# Stereo_L_R_TPA3138D2.net
KiCad netlist of a schematic drawn in Altium Designer
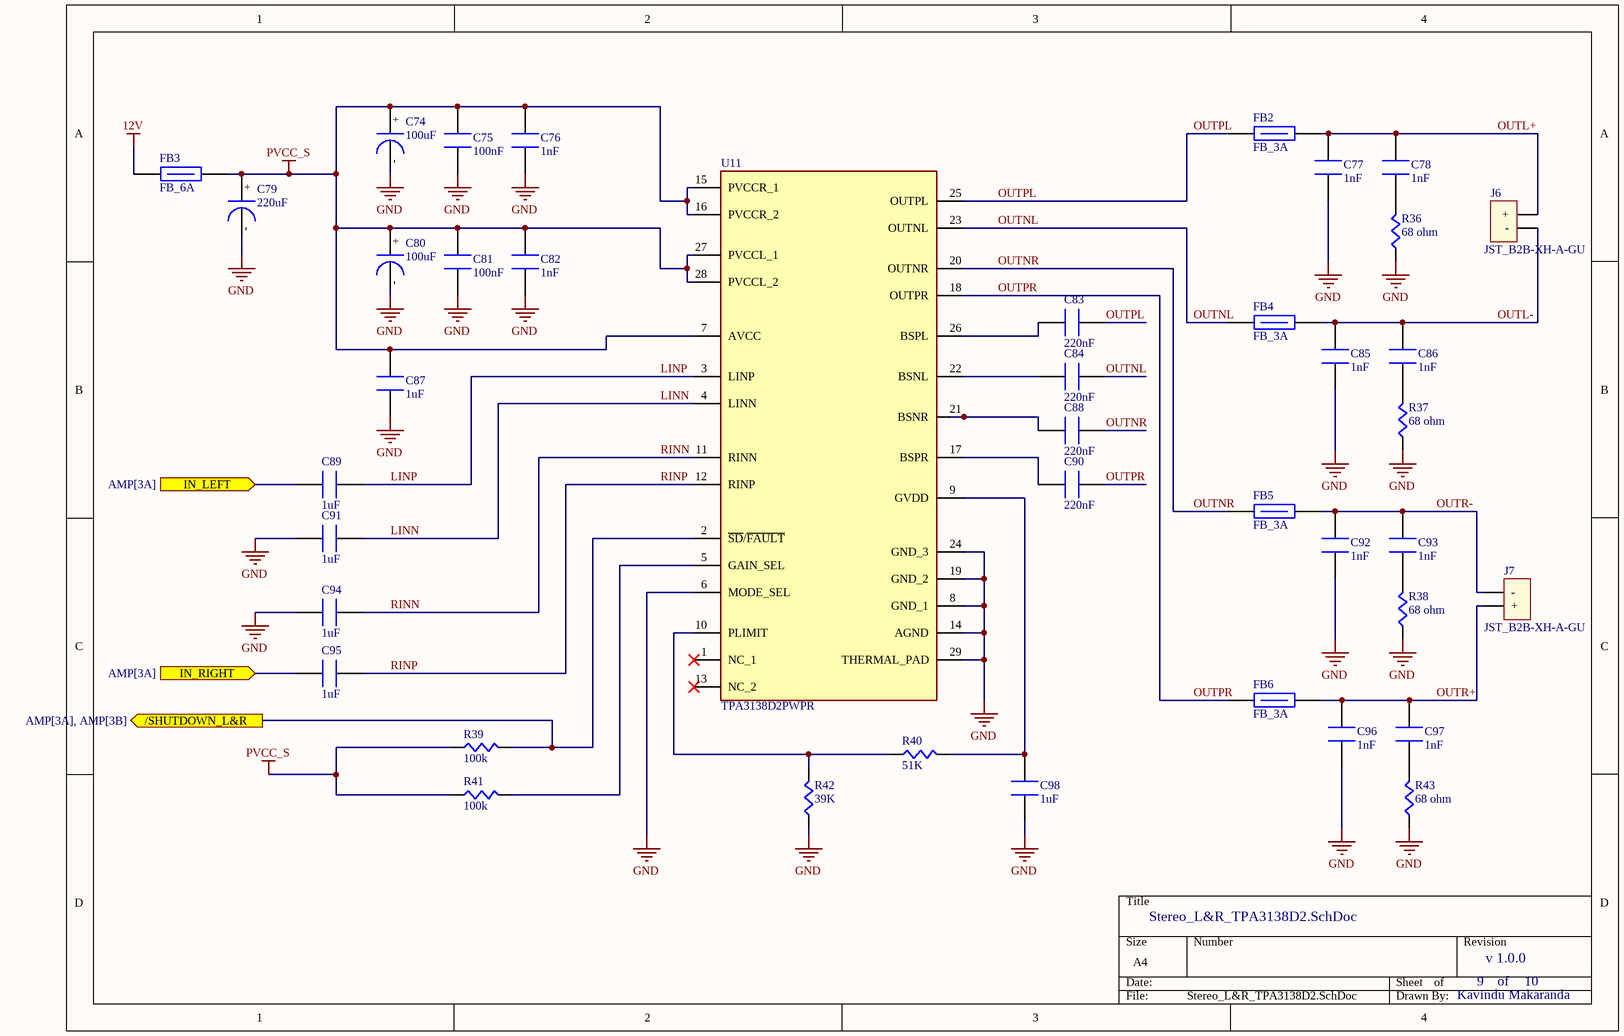
[diagram p0: Stereo_L&R_TPA3138D2.SchDoc]

(export (version "E")
  (design (tool "Eeschema 10.0.6"))
  (components
    (comp (ref "C74")
      (value "100uF")
      (footprint "CAPD6.3XL6.3X77M")
      (libsource (lib "Schlib1") (part "CPD6.3XL7.7_100uF_POLY"))
    )
    (comp (ref "C75")
      (value "100nF")
      (footprint "CAPC0603X8N")
      (libsource (lib "Schlib1") (part "CC0603_100nF_X7R"))
    )
    (comp (ref "C76")
      (value "1nF")
      (footprint "CAPC0603X8N")
      (libsource (lib "Schlib1") (part "CC0603_1nF_X7R"))
    )
    (comp (ref "C77")
      (value "1nF")
      (footprint "CAPC0603X8N")
      (description "C106246, CC0603JRNPO9BN102, 1nF 50V NP0 ±5% 0603 Multilayer Ceramic Capacitors MLCC - SMD/SMT ROHS")
      (libsource (lib "Schlib1") (part "CC0603_1nF_NPO"))
    )
    (comp (ref "C78")
      (value "1nF")
      (footprint "CAPC0603X8N")
      (description "C106246, CC0603JRNPO9BN102, 1nF 50V NP0 ±5% 0603 Multilayer Ceramic Capacitors MLCC - SMD/SMT ROHS")
      (libsource (lib "Schlib1") (part "CC0603_1nF_NPO"))
    )
    (comp (ref "C79")
      (value "220uF")
      (footprint "CAPD6.3XL6.3X77M")
      (libsource (lib "Schlib1") (part "CPD6.3XL7.7_220uF_POLY"))
    )
    (comp (ref "C80")
      (value "100uF")
      (footprint "CAPD6.3XL6.3X77M")
      (libsource (lib "Schlib1") (part "CPD6.3XL7.7_100uF_POLY"))
    )
    (comp (ref "C81")
      (value "100nF")
      (footprint "CAPC0603X8N")
      (libsource (lib "Schlib1") (part "CC0603_100nF_X7R"))
    )
    (comp (ref "C82")
      (value "1nF")
      (footprint "CAPC0603X8N")
      (libsource (lib "Schlib1") (part "CC0603_1nF_X7R"))
    )
    (comp (ref "C83")
      (value "220nF")
      (footprint "CAPC1206X18N")
      (libsource (lib "Schlib1") (part "CC1206_220nF_NPO"))
    )
    (comp (ref "C84")
      (value "220nF")
      (footprint "CAPC1206X18N")
      (libsource (lib "Schlib1") (part "CC1206_220nF_NPO"))
    )
    (comp (ref "C85")
      (value "1nF")
      (footprint "CAPC0603X8N")
      (description "C106246, CC0603JRNPO9BN102, 1nF 50V NP0 ±5% 0603 Multilayer Ceramic Capacitors MLCC - SMD/SMT ROHS")
      (libsource (lib "Schlib1") (part "CC0603_1nF_NPO"))
    )
    (comp (ref "C86")
      (value "1nF")
      (footprint "CAPC0603X8N")
      (description "C106246, CC0603JRNPO9BN102, 1nF 50V NP0 ±5% 0603 Multilayer Ceramic Capacitors MLCC - SMD/SMT ROHS")
      (libsource (lib "Schlib1") (part "CC0603_1nF_NPO"))
    )
    (comp (ref "C87")
      (value "1uF")
      (footprint "CAP0805X13N")
      (description "C28323, CL21B105KBFNNNE, 1uF 50V X7R ±10% 0805 Multilayer Ceramic Capacitors MLCC - SMD/SMT ROHS")
      (libsource (lib "Schlib1") (part "CC0805_1uF_X7R"))
    )
    (comp (ref "C88")
      (value "220nF")
      (footprint "CAPC1206X18N")
      (libsource (lib "Schlib1") (part "CC1206_220nF_NPO"))
    )
    (comp (ref "C89")
      (value "1uF")
      (footprint "CAP0805X13N")
      (description "C28323, CL21B105KBFNNNE, 1uF 50V X7R ±10% 0805 Multilayer Ceramic Capacitors MLCC - SMD/SMT ROHS")
      (libsource (lib "Schlib1") (part "CC0805_1uF_X7R"))
    )
    (comp (ref "C90")
      (value "220nF")
      (footprint "CAPC1206X18N")
      (libsource (lib "Schlib1") (part "CC1206_220nF_NPO"))
    )
    (comp (ref "C91")
      (value "1uF")
      (footprint "CAP0805X13N")
      (description "C28323, CL21B105KBFNNNE, 1uF 50V X7R ±10% 0805 Multilayer Ceramic Capacitors MLCC - SMD/SMT ROHS")
      (libsource (lib "Schlib1") (part "CC0805_1uF_X7R"))
    )
    (comp (ref "C92")
      (value "1nF")
      (footprint "CAPC0603X8N")
      (description "C106246, CC0603JRNPO9BN102, 1nF 50V NP0 ±5% 0603 Multilayer Ceramic Capacitors MLCC - SMD/SMT ROHS")
      (libsource (lib "Schlib1") (part "CC0603_1nF_NPO"))
    )
    (comp (ref "C93")
      (value "1nF")
      (footprint "CAPC0603X8N")
      (description "C106246, CC0603JRNPO9BN102, 1nF 50V NP0 ±5% 0603 Multilayer Ceramic Capacitors MLCC - SMD/SMT ROHS")
      (libsource (lib "Schlib1") (part "CC0603_1nF_NPO"))
    )
    (comp (ref "C94")
      (value "1uF")
      (footprint "CAP0805X13N")
      (description "C28323, CL21B105KBFNNNE, 1uF 50V X7R ±10% 0805 Multilayer Ceramic Capacitors MLCC - SMD/SMT ROHS")
      (libsource (lib "Schlib1") (part "CC0805_1uF_X7R"))
    )
    (comp (ref "C95")
      (value "1uF")
      (footprint "CAP0805X13N")
      (description "C28323, CL21B105KBFNNNE, 1uF 50V X7R ±10% 0805 Multilayer Ceramic Capacitors MLCC - SMD/SMT ROHS")
      (libsource (lib "Schlib1") (part "CC0805_1uF_X7R"))
    )
    (comp (ref "C96")
      (value "1nF")
      (footprint "CAPC0603X8N")
      (description "C106246, CC0603JRNPO9BN102, 1nF 50V NP0 ±5% 0603 Multilayer Ceramic Capacitors MLCC - SMD/SMT ROHS")
      (libsource (lib "Schlib1") (part "CC0603_1nF_NPO"))
    )
    (comp (ref "C97")
      (value "1nF")
      (footprint "CAPC0603X8N")
      (description "C106246, CC0603JRNPO9BN102, 1nF 50V NP0 ±5% 0603 Multilayer Ceramic Capacitors MLCC - SMD/SMT ROHS")
      (libsource (lib "Schlib1") (part "CC0603_1nF_NPO"))
    )
    (comp (ref "C98")
      (value "1uF")
      (footprint "CAP0805X13N")
      (description "C28323, CL21B105KBFNNNE, 1uF 50V X7R ±10% 0805 Multilayer Ceramic Capacitors MLCC - SMD/SMT ROHS")
      (libsource (lib "Schlib1") (part "CC0805_1uF_X7R"))
    )
    (comp (ref "FB2")
      (value "FB_3A")
      (footprint "FB0603X08N")
      (description "C107332, MPZ1608S101ATAH0, -55℃~+125℃ 1 100Ω@100MHz 30mΩ 3A ±25% 0603 Ferrite Beads ROHS")
      (libsource (lib "Schlib1") (part "FB0603_3A"))
    )
    (comp (ref "FB3")
      (value "FB_6A")
      (footprint "FB0805X12N")
      (description "C136227, MPZ2012S300AT000, -55℃~+125℃ 1 10mΩ 30Ω@100MHz 6A ±25% 0805 Ferrite Beads ROHS")
      (libsource (lib "Schlib1") (part "FB0805_6A"))
    )
    (comp (ref "FB4")
      (value "FB_3A")
      (footprint "FB0603X08N")
      (description "C107332, MPZ1608S101ATAH0, -55℃~+125℃ 1 100Ω@100MHz 30mΩ 3A ±25% 0603 Ferrite Beads ROHS")
      (libsource (lib "Schlib1") (part "FB0603_3A"))
    )
    (comp (ref "FB5")
      (value "FB_3A")
      (footprint "FB0603X08N")
      (description "C107332, MPZ1608S101ATAH0, -55℃~+125℃ 1 100Ω@100MHz 30mΩ 3A ±25% 0603 Ferrite Beads ROHS")
      (libsource (lib "Schlib1") (part "FB0603_3A"))
    )
    (comp (ref "FB6")
      (value "FB_3A")
      (footprint "FB0603X08N")
      (description "C107332, MPZ1608S101ATAH0, -55℃~+125℃ 1 100Ω@100MHz 30mΩ 3A ±25% 0603 Ferrite Beads ROHS")
      (libsource (lib "Schlib1") (part "FB0603_3A"))
    )
    (comp (ref "J6")
      (value "JST_B2B-XH-A-GU")
      (footprint "JST_B2B_XH_A_GU")
      (libsource (lib "") (part "JST_B2B-XH-A-GU_1"))
    )
    (comp (ref "J7")
      (value "JST_B2B-XH-A-GU")
      (footprint "JST_B2B_XH_A_GU")
      (libsource (lib "Schlib1") (part "JST_B2B-XH-A-GU"))
    )
    (comp (ref "R36")
      (value "68 ohm")
      (footprint "RECS0603X45N")
      (libsource (lib "Schlib1") (part "RESC0603_68_THIN"))
    )
    (comp (ref "R37")
      (value "68 ohm")
      (footprint "RECS0603X45N")
      (libsource (lib "Schlib1") (part "RESC0603_68_THIN"))
    )
    (comp (ref "R38")
      (value "68 ohm")
      (footprint "RECS0603X45N")
      (libsource (lib "Schlib1") (part "RESC0603_68_THIN"))
    )
    (comp (ref "R39")
      (value "100k")
      (footprint "RECS0603X45N")
      (libsource (lib "Schlib1") (part "RESC0603_100K_THIN"))
    )
    (comp (ref "R40")
      (value "51K")
      (footprint "RECS0603X45N")
      (libsource (lib "Schlib1") (part "RESC0603_51K_THICK"))
    )
    (comp (ref "R41")
      (value "100k")
      (footprint "RECS0603X45N")
      (libsource (lib "Schlib1") (part "RESC0603_100K_THIN"))
    )
    (comp (ref "R42")
      (value "39K")
      (footprint "RECS0603X45N")
      (libsource (lib "Schlib1") (part "RESC0603_39K_THICK"))
    )
    (comp (ref "R43")
      (value "68 ohm")
      (footprint "RECS0603X45N")
      (libsource (lib "Schlib1") (part "RESC0603_68_THIN"))
    )
    (comp (ref "U11")
      (value "TPA3138D2PWPR")
      (footprint "SOP65P640X120-29N")
      (fields (field (name "MOUSER PART NUMBER") "595-TPA3138D2PWPR"))
      (libsource (lib "Schlib1") (part "TPA3138D2PWPR"))
    )
  )
  (nets
    (net (code "1") (name "/IN_LEFT") (class "Default")
      (node (ref "C89") (pin "1") (pinfunction "1_1") (pintype "passive"))
    )
    (net (code "2") (name "/IN_RIGHT") (class "Default")
      (node (ref "C95") (pin "1") (pinfunction "1_1") (pintype "passive"))
    )
    (net (code "3") (name "/LINN") (class "Default")
      (node (ref "C91") (pin "2") (pinfunction "2_2") (pintype "passive"))
      (node (ref "U11") (pin "4") (pinfunction "LINN_4") (pintype "passive"))
    )
    (net (code "4") (name "/LINP") (class "Default")
      (node (ref "C89") (pin "2") (pinfunction "2_2") (pintype "passive"))
      (node (ref "U11") (pin "3") (pinfunction "LINP_3") (pintype "passive"))
    )
    (net (code "5") (name "/OUTL+") (class "Default")
      (node (ref "C77") (pin "2") (pinfunction "2_2") (pintype "passive"))
      (node (ref "C78") (pin "2") (pinfunction "2_2") (pintype "passive"))
      (node (ref "FB2") (pin "2") (pinfunction "2_2") (pintype "passive"))
      (node (ref "J6") (pin "1") (pinfunction "+_1") (pintype "passive"))
    )
    (net (code "6") (name "/OUTL-") (class "Default")
      (node (ref "C85") (pin "2") (pinfunction "2_2") (pintype "passive"))
      (node (ref "C86") (pin "2") (pinfunction "2_2") (pintype "passive"))
      (node (ref "FB4") (pin "2") (pinfunction "2_2") (pintype "passive"))
      (node (ref "J6") (pin "2") (pinfunction "-_2") (pintype "passive"))
    )
    (net (code "7") (name "/OUTNL") (class "Default")
      (node (ref "C84") (pin "2") (pinfunction "2_2") (pintype "passive"))
      (node (ref "FB4") (pin "1") (pinfunction "1_1") (pintype "passive"))
      (node (ref "U11") (pin "23") (pinfunction "OUTNL_23") (pintype "passive"))
    )
    (net (code "8") (name "/OUTNR") (class "Default")
      (node (ref "C88") (pin "2") (pinfunction "2_2") (pintype "passive"))
      (node (ref "FB5") (pin "1") (pinfunction "1_1") (pintype "passive"))
      (node (ref "U11") (pin "20") (pinfunction "OUTNR_20") (pintype "passive"))
    )
    (net (code "9") (name "/OUTPL") (class "Default")
      (node (ref "C83") (pin "2") (pinfunction "2_2") (pintype "passive"))
      (node (ref "FB2") (pin "1") (pinfunction "1_1") (pintype "passive"))
      (node (ref "U11") (pin "25") (pinfunction "OUTPL_25") (pintype "passive"))
    )
    (net (code "10") (name "/OUTPR") (class "Default")
      (node (ref "C90") (pin "2") (pinfunction "2_2") (pintype "passive"))
      (node (ref "FB6") (pin "1") (pinfunction "1_1") (pintype "passive"))
      (node (ref "U11") (pin "18") (pinfunction "OUTPR_18") (pintype "passive"))
    )
    (net (code "11") (name "/OUTR+") (class "Default")
      (node (ref "C96") (pin "2") (pinfunction "2_2") (pintype "passive"))
      (node (ref "C97") (pin "2") (pinfunction "2_2") (pintype "passive"))
      (node (ref "FB6") (pin "2") (pinfunction "2_2") (pintype "passive"))
      (node (ref "J7") (pin "1") (pinfunction "+_1") (pintype "passive"))
    )
    (net (code "12") (name "/OUTR-") (class "Default")
      (node (ref "C92") (pin "2") (pinfunction "2_2") (pintype "passive"))
      (node (ref "C93") (pin "2") (pinfunction "2_2") (pintype "passive"))
      (node (ref "FB5") (pin "2") (pinfunction "2_2") (pintype "passive"))
      (node (ref "J7") (pin "2") (pinfunction "-_2") (pintype "passive"))
    )
    (net (code "13") (name "/RINN") (class "Default")
      (node (ref "C94") (pin "2") (pinfunction "2_2") (pintype "passive"))
      (node (ref "U11") (pin "11") (pinfunction "RINN_11") (pintype "passive"))
    )
    (net (code "14") (name "/RINP") (class "Default")
      (node (ref "C95") (pin "2") (pinfunction "2_2") (pintype "passive"))
      (node (ref "U11") (pin "12") (pinfunction "RINP_12") (pintype "passive"))
    )
    (net (code "15") (name "/{slash}SHUTDOWN_L&R") (class "Default")
      (node (ref "R39") (pin "2") (pinfunction "2_2") (pintype "passive"))
      (node (ref "U11") (pin "2") (pinfunction "~{SD}/~{FAULT}_2") (pintype "passive"))
    )
    (net (code "16") (name "12V") (class "Default")
      (node (ref "FB3") (pin "1") (pinfunction "1_1") (pintype "passive"))
    )
    (net (code "17") (name "GND") (class "Default")
      (node (ref "C74") (pin "2") (pinfunction "2_2") (pintype "passive"))
      (node (ref "C75") (pin "1") (pinfunction "1_1") (pintype "passive"))
      (node (ref "C76") (pin "1") (pinfunction "1_1") (pintype "passive"))
      (node (ref "C77") (pin "1") (pinfunction "1_1") (pintype "passive"))
      (node (ref "C79") (pin "2") (pinfunction "2_2") (pintype "passive"))
      (node (ref "C80") (pin "2") (pinfunction "2_2") (pintype "passive"))
      (node (ref "C81") (pin "1") (pinfunction "1_1") (pintype "passive"))
      (node (ref "C82") (pin "1") (pinfunction "1_1") (pintype "passive"))
      (node (ref "C85") (pin "1") (pinfunction "1_1") (pintype "passive"))
      (node (ref "C87") (pin "1") (pinfunction "1_1") (pintype "passive"))
      (node (ref "C91") (pin "1") (pinfunction "1_1") (pintype "passive"))
      (node (ref "C92") (pin "1") (pinfunction "1_1") (pintype "passive"))
      (node (ref "C94") (pin "1") (pinfunction "1_1") (pintype "passive"))
      (node (ref "C96") (pin "1") (pinfunction "1_1") (pintype "passive"))
      (node (ref "C98") (pin "1") (pinfunction "1_1") (pintype "passive"))
      (node (ref "R36") (pin "1") (pinfunction "1_1") (pintype "passive"))
      (node (ref "R37") (pin "1") (pinfunction "1_1") (pintype "passive"))
      (node (ref "R38") (pin "1") (pinfunction "1_1") (pintype "passive"))
      (node (ref "R42") (pin "1") (pinfunction "1_1") (pintype "passive"))
      (node (ref "R43") (pin "1") (pinfunction "1_1") (pintype "passive"))
      (node (ref "U11") (pin "14") (pinfunction "AGND_14") (pintype "passive"))
      (node (ref "U11") (pin "19") (pinfunction "GND_2_19") (pintype "passive"))
      (node (ref "U11") (pin "24") (pinfunction "GND_3_24") (pintype "passive"))
      (node (ref "U11") (pin "29") (pinfunction "THERMAL_PAD_29") (pintype "passive"))
      (node (ref "U11") (pin "6") (pinfunction "MODE_SEL_6") (pintype "passive"))
      (node (ref "U11") (pin "8") (pinfunction "GND_1_8") (pintype "passive"))
    )
    (net (code "18") (name "Net-(C78-Pad1)") (class "Default")
      (node (ref "C78") (pin "1") (pinfunction "1_1") (pintype "passive"))
      (node (ref "R36") (pin "2") (pinfunction "2_2") (pintype "passive"))
    )
    (net (code "19") (name "Net-(C86-Pad1)") (class "Default")
      (node (ref "C86") (pin "1") (pinfunction "1_1") (pintype "passive"))
      (node (ref "R37") (pin "2") (pinfunction "2_2") (pintype "passive"))
    )
    (net (code "20") (name "Net-(C93-Pad1)") (class "Default")
      (node (ref "C93") (pin "1") (pinfunction "1_1") (pintype "passive"))
      (node (ref "R38") (pin "2") (pinfunction "2_2") (pintype "passive"))
    )
    (net (code "21") (name "Net-(C97-Pad1)") (class "Default")
      (node (ref "C97") (pin "1") (pinfunction "1_1") (pintype "passive"))
      (node (ref "R43") (pin "2") (pinfunction "2_2") (pintype "passive"))
    )
    (net (code "22") (name "Net-(U11-BSNL)") (class "Default")
      (node (ref "C84") (pin "1") (pinfunction "1_1") (pintype "passive"))
      (node (ref "U11") (pin "22") (pinfunction "BSNL_22") (pintype "passive"))
    )
    (net (code "23") (name "Net-(U11-BSNR)") (class "Default")
      (node (ref "C88") (pin "1") (pinfunction "1_1") (pintype "passive"))
      (node (ref "U11") (pin "21") (pinfunction "BSNR_21") (pintype "passive"))
    )
    (net (code "24") (name "Net-(U11-BSPL)") (class "Default")
      (node (ref "C83") (pin "1") (pinfunction "1_1") (pintype "passive"))
      (node (ref "U11") (pin "26") (pinfunction "BSPL_26") (pintype "passive"))
    )
    (net (code "25") (name "Net-(U11-BSPR)") (class "Default")
      (node (ref "C90") (pin "1") (pinfunction "1_1") (pintype "passive"))
      (node (ref "U11") (pin "17") (pinfunction "BSPR_17") (pintype "passive"))
    )
    (net (code "26") (name "Net-(U11-GAIN_SEL)") (class "Default")
      (node (ref "R41") (pin "2") (pinfunction "2_2") (pintype "passive"))
      (node (ref "U11") (pin "5") (pinfunction "GAIN_SEL_5") (pintype "passive"))
    )
    (net (code "27") (name "Net-(U11-GVDD)") (class "Default")
      (node (ref "C98") (pin "2") (pinfunction "2_2") (pintype "passive"))
      (node (ref "R40") (pin "2") (pinfunction "2_2") (pintype "passive"))
      (node (ref "U11") (pin "9") (pinfunction "GVDD_9") (pintype "passive"))
    )
    (net (code "28") (name "Net-(U11-PLIMIT)") (class "Default")
      (node (ref "R40") (pin "1") (pinfunction "1_1") (pintype "passive"))
      (node (ref "R42") (pin "2") (pinfunction "2_2") (pintype "passive"))
      (node (ref "U11") (pin "10") (pinfunction "PLIMIT_10") (pintype "passive"))
    )
    (net (code "29") (name "PVCC_S") (class "Default")
      (node (ref "C74") (pin "1") (pinfunction "1_1") (pintype "passive"))
      (node (ref "C75") (pin "2") (pinfunction "2_2") (pintype "passive"))
      (node (ref "C76") (pin "2") (pinfunction "2_2") (pintype "passive"))
      (node (ref "C79") (pin "1") (pinfunction "1_1") (pintype "passive"))
      (node (ref "C80") (pin "1") (pinfunction "1_1") (pintype "passive"))
      (node (ref "C81") (pin "2") (pinfunction "2_2") (pintype "passive"))
      (node (ref "C82") (pin "2") (pinfunction "2_2") (pintype "passive"))
      (node (ref "C87") (pin "2") (pinfunction "2_2") (pintype "passive"))
      (node (ref "FB3") (pin "2") (pinfunction "2_2") (pintype "passive"))
      (node (ref "R39") (pin "1") (pinfunction "1_1") (pintype "passive"))
      (node (ref "R41") (pin "1") (pinfunction "1_1") (pintype "passive"))
      (node (ref "U11") (pin "15") (pinfunction "PVCCR_1_15") (pintype "passive"))
      (node (ref "U11") (pin "16") (pinfunction "PVCCR_2_16") (pintype "passive"))
      (node (ref "U11") (pin "27") (pinfunction "PVCCL_1_27") (pintype "passive"))
      (node (ref "U11") (pin "28") (pinfunction "PVCCL_2_28") (pintype "passive"))
      (node (ref "U11") (pin "7") (pinfunction "AVCC_7") (pintype "passive"))
    )
    (net (code "30") (name "unconnected-(U11-NC_1-Pad1)") (class "Default")
      (node (ref "U11") (pin "1") (pinfunction "NC_1_1") (pintype "passive+no_connect"))
    )
    (net (code "31") (name "unconnected-(U11-NC_2-Pad13)") (class "Default")
      (node (ref "U11") (pin "13") (pinfunction "NC_2_13") (pintype "passive+no_connect"))
    )
  )
)
